# 82_SATA-SATA_PM0.net
KiCad netlist of a schematic drawn in Altium Designer
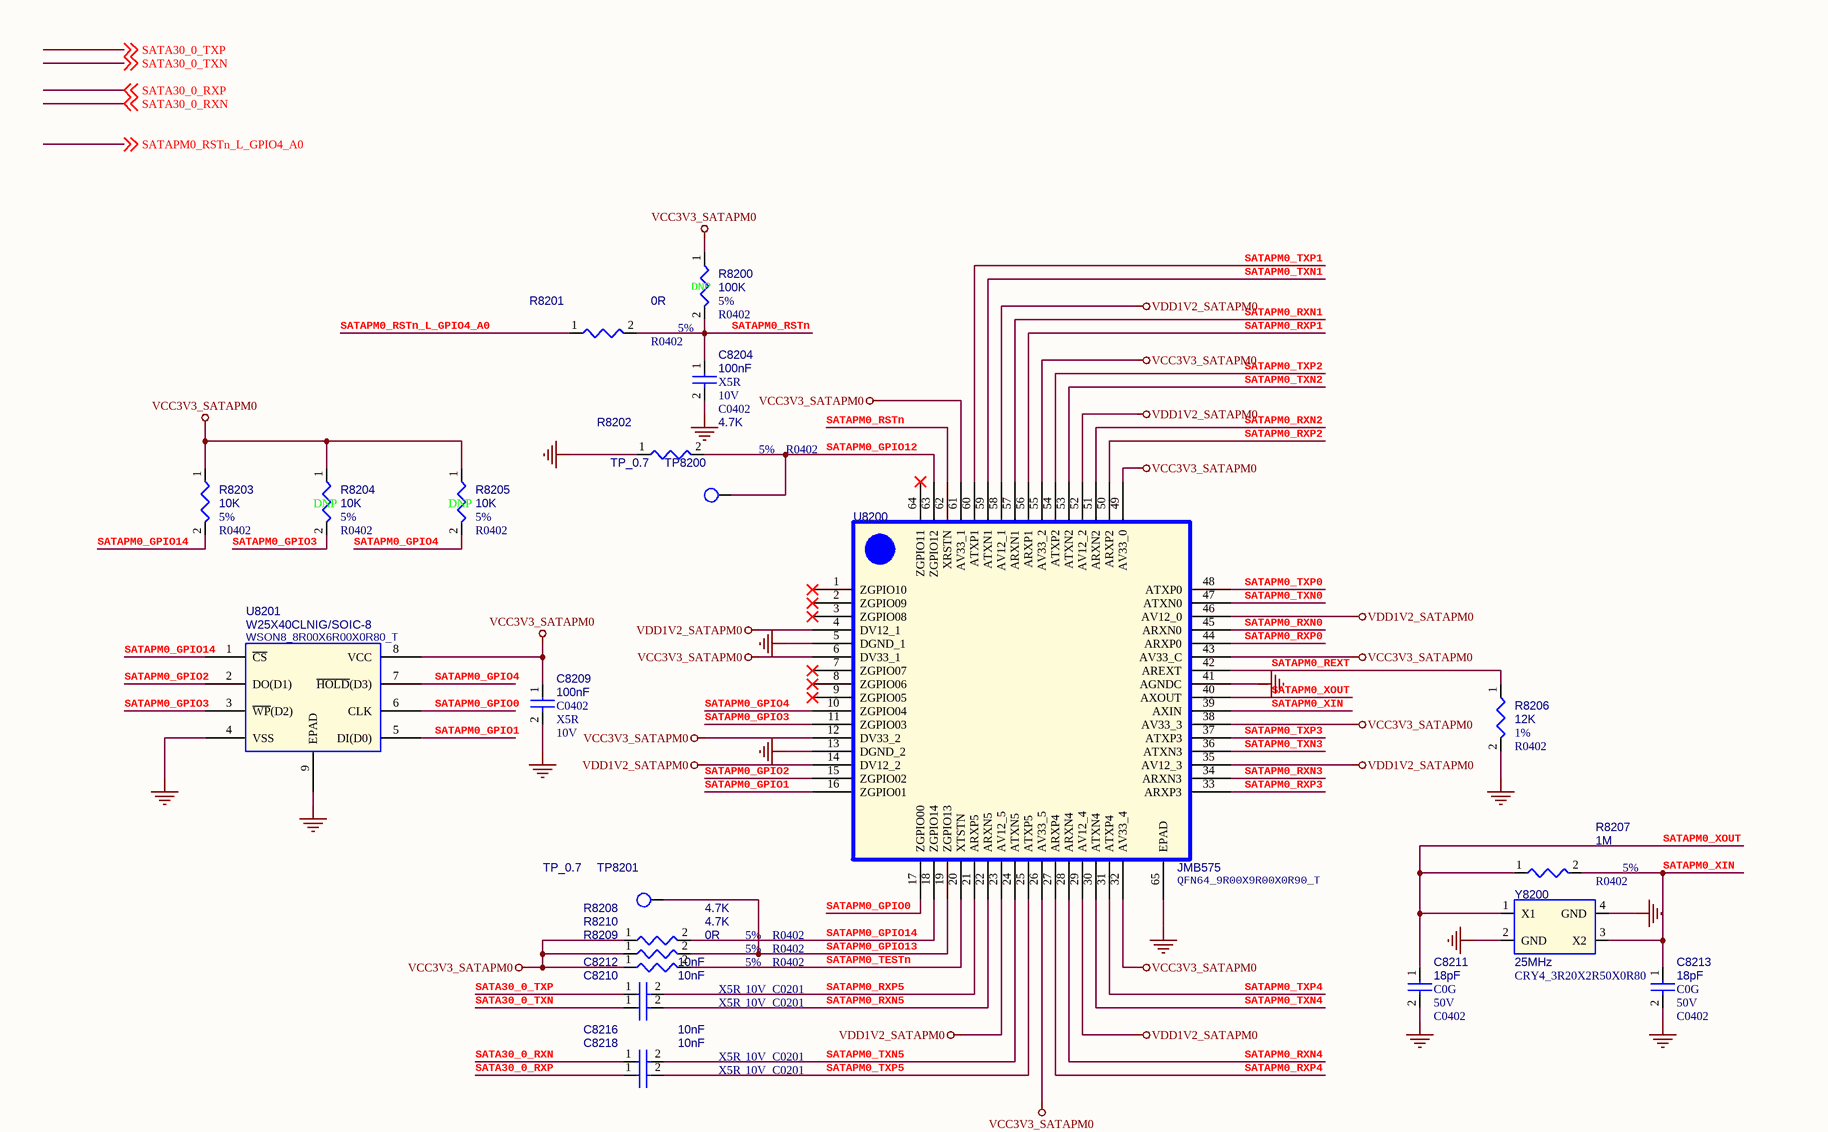
[diagram p0: 82.SATA-SATA PM0.SchDoc, top left]
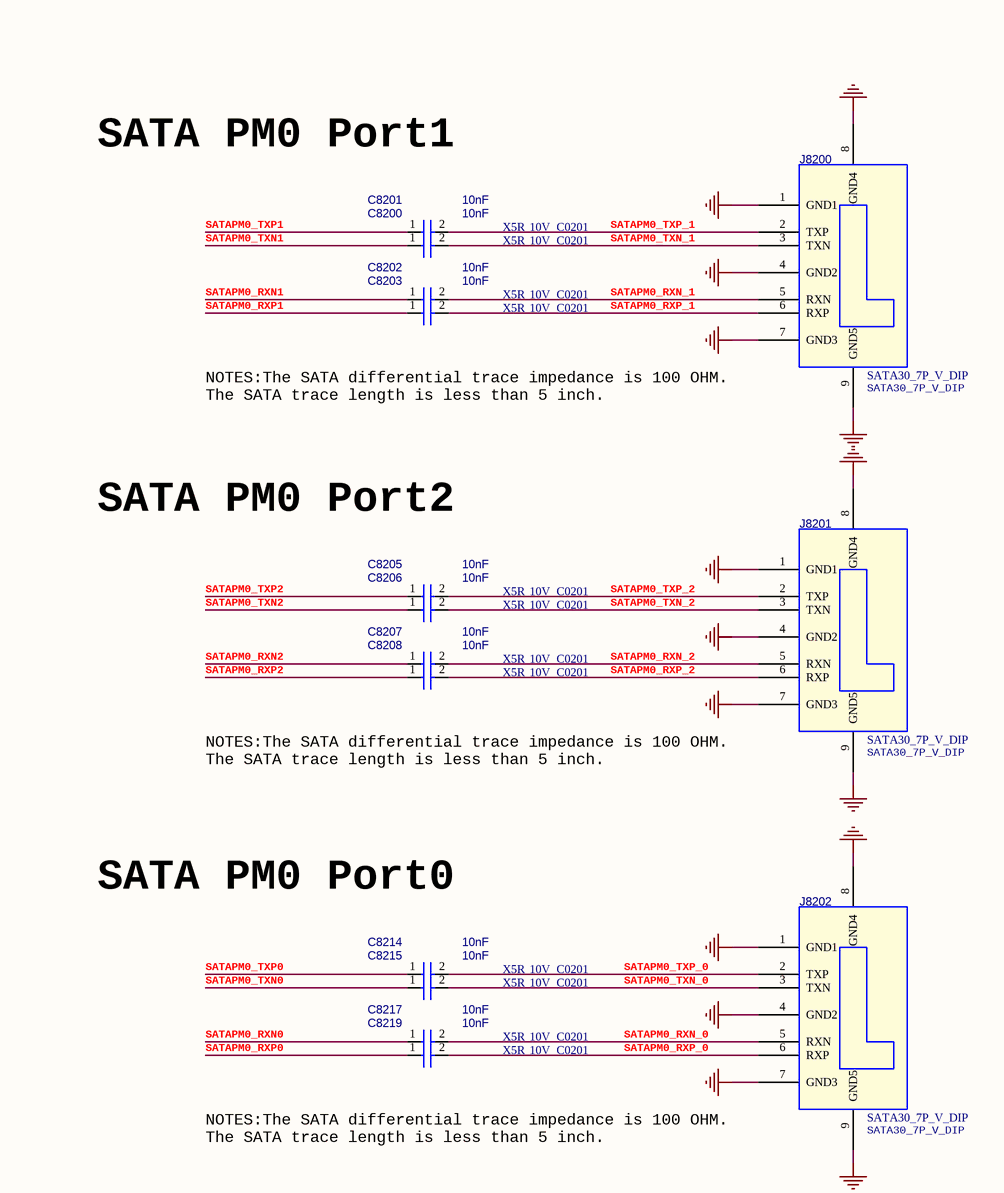
[diagram p1: 82.SATA-SATA PM0.SchDoc, top right]
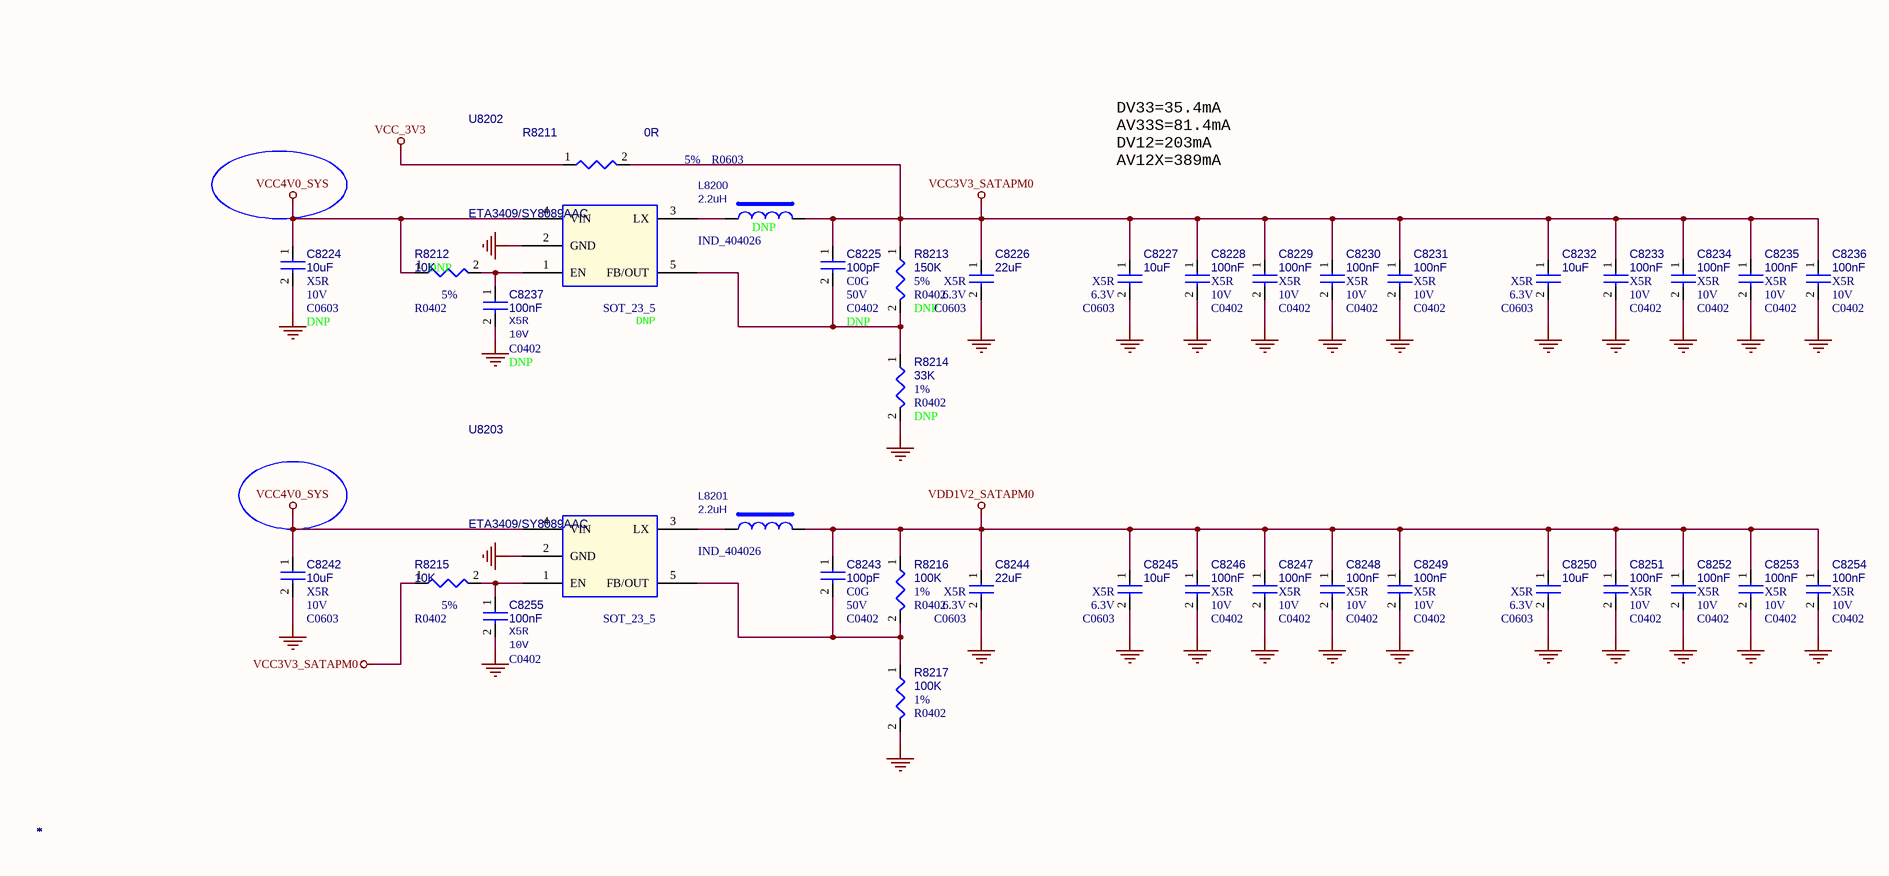
[diagram p2: 82.SATA-SATA PM0.SchDoc, bottom left]
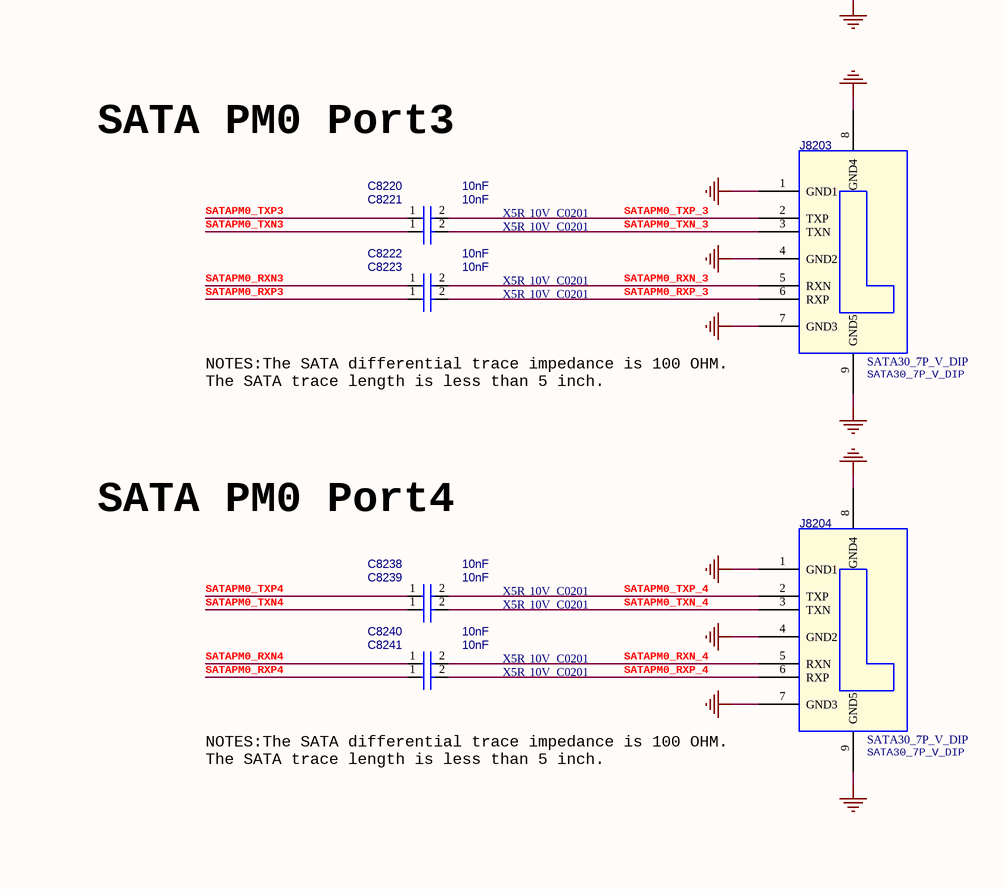
[diagram p3: 82.SATA-SATA PM0.SchDoc, bottom right]

(export (version "E")
  (design (tool "Eeschema 10.0.6"))
  (components
    (comp (ref "C8200")
      (value "*")
      (footprint "C0201")
      (description "cap,10.00nF,+/-10%,10V,X5R,C0201")
      (fields
        (field (name "VOLTAGE") "10V")
        (field (name "PCB FOOTPRINT") "C0201")
        (field (name "DIELECTRIC") "X5R")
        (field (name "MANUFACTURER") "TDK")
        (field (name "TOLERANCE") "10%")
        (field (name "ALTIUM_UNNAMED_1") "10nF")
        (field (name "CREATED BY") "JJJ")
      )
      (libsource (lib "*") (part "CAP NP"))
    )
    (comp (ref "C8201")
      (value "*")
      (footprint "C0201")
      (description "cap,10.00nF,+/-10%,10V,X5R,C0201")
      (fields
        (field (name "VOLTAGE") "10V")
        (field (name "PCB FOOTPRINT") "C0201")
        (field (name "DIELECTRIC") "X5R")
        (field (name "MANUFACTURER") "TDK")
        (field (name "TOLERANCE") "10%")
        (field (name "ALTIUM_UNNAMED_1") "10nF")
        (field (name "CREATED BY") "JJJ")
      )
      (libsource (lib "*") (part "CAP NP"))
    )
    (comp (ref "C8202")
      (value "*")
      (footprint "C0201")
      (description "cap,10.00nF,+/-10%,10V,X5R,C0201")
      (fields
        (field (name "VOLTAGE") "10V")
        (field (name "PCB FOOTPRINT") "C0201")
        (field (name "DIELECTRIC") "X5R")
        (field (name "MANUFACTURER") "TDK")
        (field (name "TOLERANCE") "10%")
        (field (name "ALTIUM_UNNAMED_1") "10nF")
        (field (name "CREATED BY") "JJJ")
      )
      (libsource (lib "*") (part "CAP NP"))
    )
    (comp (ref "C8203")
      (value "*")
      (footprint "C0201")
      (description "cap,10.00nF,+/-10%,10V,X5R,C0201")
      (fields
        (field (name "VOLTAGE") "10V")
        (field (name "PCB FOOTPRINT") "C0201")
        (field (name "DIELECTRIC") "X5R")
        (field (name "MANUFACTURER") "TDK")
        (field (name "TOLERANCE") "10%")
        (field (name "ALTIUM_UNNAMED_1") "10nF")
        (field (name "CREATED BY") "JJJ")
      )
      (libsource (lib "*") (part "CAP NP"))
    )
    (comp (ref "C8204")
      (value "*")
      (footprint "C0402")
      (description "cap,100.00nF,+/-10%,10V,X5R,C0402")
      (fields
        (field (name "VOLTAGE") "10V")
        (field (name "PCB FOOTPRINT") "C0402")
        (field (name "DIELECTRIC") "X5R")
        (field (name "TOLERANCE") "10%")
        (field (name "MANUFACTURER") "TDK")
        (field (name "ALTIUM_UNNAMED_1") "100nF")
        (field (name "CREATED BY") "JJJ")
      )
      (libsource (lib "*") (part "CAP NP"))
    )
    (comp (ref "C8205")
      (value "*")
      (footprint "C0201")
      (description "cap,10.00nF,+/-10%,10V,X5R,C0201")
      (fields
        (field (name "VOLTAGE") "10V")
        (field (name "PCB FOOTPRINT") "C0201")
        (field (name "DIELECTRIC") "X5R")
        (field (name "MANUFACTURER") "TDK")
        (field (name "TOLERANCE") "10%")
        (field (name "ALTIUM_UNNAMED_1") "10nF")
        (field (name "CREATED BY") "JJJ")
      )
      (libsource (lib "*") (part "CAP NP"))
    )
    (comp (ref "C8206")
      (value "*")
      (footprint "C0201")
      (description "cap,10.00nF,+/-10%,10V,X5R,C0201")
      (fields
        (field (name "VOLTAGE") "10V")
        (field (name "PCB FOOTPRINT") "C0201")
        (field (name "DIELECTRIC") "X5R")
        (field (name "MANUFACTURER") "TDK")
        (field (name "TOLERANCE") "10%")
        (field (name "ALTIUM_UNNAMED_1") "10nF")
        (field (name "CREATED BY") "JJJ")
      )
      (libsource (lib "*") (part "CAP NP"))
    )
    (comp (ref "C8207")
      (value "*")
      (footprint "C0201")
      (description "cap,10.00nF,+/-10%,10V,X5R,C0201")
      (fields
        (field (name "VOLTAGE") "10V")
        (field (name "PCB FOOTPRINT") "C0201")
        (field (name "DIELECTRIC") "X5R")
        (field (name "MANUFACTURER") "TDK")
        (field (name "TOLERANCE") "10%")
        (field (name "ALTIUM_UNNAMED_1") "10nF")
        (field (name "CREATED BY") "JJJ")
      )
      (libsource (lib "*") (part "CAP NP"))
    )
    (comp (ref "C8208")
      (value "*")
      (footprint "C0201")
      (description "cap,10.00nF,+/-10%,10V,X5R,C0201")
      (fields
        (field (name "VOLTAGE") "10V")
        (field (name "PCB FOOTPRINT") "C0201")
        (field (name "DIELECTRIC") "X5R")
        (field (name "MANUFACTURER") "TDK")
        (field (name "TOLERANCE") "10%")
        (field (name "ALTIUM_UNNAMED_1") "10nF")
        (field (name "CREATED BY") "JJJ")
      )
      (libsource (lib "*") (part "CAP NP"))
    )
    (comp (ref "C8209")
      (value "*")
      (footprint "C0402")
      (description "cap,100.00nF,+/-10%,10V,X5R,C0402")
      (fields
        (field (name "VOLTAGE") "10V")
        (field (name "PCB FOOTPRINT") "C0402")
        (field (name "DIELECTRIC") "X5R")
        (field (name "TOLERANCE") "10%")
        (field (name "MANUFACTURER") "TDK")
        (field (name "ALTIUM_UNNAMED_1") "100nF")
        (field (name "CREATED BY") "JJJ")
      )
      (libsource (lib "*") (part "CAP NP"))
    )
    (comp (ref "C8210")
      (value "*")
      (footprint "C0201")
      (description "cap,10.00nF,+/-10%,10V,X5R,C0201")
      (fields
        (field (name "VOLTAGE") "10V")
        (field (name "PCB FOOTPRINT") "C0201")
        (field (name "DIELECTRIC") "X5R")
        (field (name "TOLERANCE") "10%")
        (field (name "MANUFACTURER") "TDK")
        (field (name "ALTIUM_UNNAMED_1") "10nF")
        (field (name "CREATED BY") "JJJ")
      )
      (libsource (lib "*") (part "CAP NP"))
    )
    (comp (ref "C8211")
      (value "*")
      (footprint "C0402")
      (description "cap,18.00pF,+/-5%,50V,C0G,C0402")
      (fields
        (field (name "VOLTAGE") "50V")
        (field (name "PCB FOOTPRINT") "C0402")
        (field (name "DIELECTRIC") "C0G")
        (field (name "TOLERANCE") "5%")
        (field (name "MANUFACTURER") "TDK")
        (field (name "ALTIUM_UNNAMED_1") "18pF")
        (field (name "CREATED BY") "JJJ")
      )
      (libsource (lib "*") (part "CAP NP"))
    )
    (comp (ref "C8212")
      (value "*")
      (footprint "C0201")
      (description "cap,10.00nF,+/-10%,10V,X5R,C0201")
      (fields
        (field (name "VOLTAGE") "10V")
        (field (name "PCB FOOTPRINT") "C0201")
        (field (name "DIELECTRIC") "X5R")
        (field (name "TOLERANCE") "10%")
        (field (name "MANUFACTURER") "TDK")
        (field (name "ALTIUM_UNNAMED_1") "10nF")
        (field (name "CREATED BY") "JJJ")
      )
      (libsource (lib "*") (part "CAP NP"))
    )
    (comp (ref "C8213")
      (value "*")
      (footprint "C0402")
      (description "cap,18.00pF,+/-5%,50V,C0G,C0402")
      (fields
        (field (name "VOLTAGE") "50V")
        (field (name "PCB FOOTPRINT") "C0402")
        (field (name "DIELECTRIC") "C0G")
        (field (name "TOLERANCE") "5%")
        (field (name "MANUFACTURER") "TDK")
        (field (name "ALTIUM_UNNAMED_1") "18pF")
        (field (name "CREATED BY") "JJJ")
      )
      (libsource (lib "*") (part "CAP NP"))
    )
    (comp (ref "C8214")
      (value "*")
      (footprint "C0201")
      (description "cap,10.00nF,+/-10%,10V,X5R,C0201")
      (fields
        (field (name "VOLTAGE") "10V")
        (field (name "PCB FOOTPRINT") "C0201")
        (field (name "DIELECTRIC") "X5R")
        (field (name "MANUFACTURER") "TDK")
        (field (name "TOLERANCE") "10%")
        (field (name "ALTIUM_UNNAMED_1") "10nF")
        (field (name "CREATED BY") "JJJ")
      )
      (libsource (lib "*") (part "CAP NP"))
    )
    (comp (ref "C8215")
      (value "*")
      (footprint "C0201")
      (description "cap,10.00nF,+/-10%,10V,X5R,C0201")
      (fields
        (field (name "VOLTAGE") "10V")
        (field (name "PCB FOOTPRINT") "C0201")
        (field (name "DIELECTRIC") "X5R")
        (field (name "MANUFACTURER") "TDK")
        (field (name "TOLERANCE") "10%")
        (field (name "ALTIUM_UNNAMED_1") "10nF")
        (field (name "CREATED BY") "JJJ")
      )
      (libsource (lib "*") (part "CAP NP"))
    )
    (comp (ref "C8216")
      (value "*")
      (footprint "C0201")
      (description "cap,10.00nF,+/-10%,10V,X5R,C0201")
      (fields
        (field (name "VOLTAGE") "10V")
        (field (name "PCB FOOTPRINT") "C0201")
        (field (name "DIELECTRIC") "X5R")
        (field (name "TOLERANCE") "10%")
        (field (name "MANUFACTURER") "TDK")
        (field (name "ALTIUM_UNNAMED_1") "10nF")
        (field (name "CREATED BY") "JJJ")
      )
      (libsource (lib "*") (part "CAP NP"))
    )
    (comp (ref "C8217")
      (value "*")
      (footprint "C0201")
      (description "cap,10.00nF,+/-10%,10V,X5R,C0201")
      (fields
        (field (name "VOLTAGE") "10V")
        (field (name "PCB FOOTPRINT") "C0201")
        (field (name "DIELECTRIC") "X5R")
        (field (name "MANUFACTURER") "TDK")
        (field (name "TOLERANCE") "10%")
        (field (name "ALTIUM_UNNAMED_1") "10nF")
        (field (name "CREATED BY") "JJJ")
      )
      (libsource (lib "*") (part "CAP NP"))
    )
    (comp (ref "C8218")
      (value "*")
      (footprint "C0201")
      (description "cap,10.00nF,+/-10%,10V,X5R,C0201")
      (fields
        (field (name "VOLTAGE") "10V")
        (field (name "PCB FOOTPRINT") "C0201")
        (field (name "DIELECTRIC") "X5R")
        (field (name "TOLERANCE") "10%")
        (field (name "MANUFACTURER") "TDK")
        (field (name "ALTIUM_UNNAMED_1") "10nF")
        (field (name "CREATED BY") "JJJ")
      )
      (libsource (lib "*") (part "CAP NP"))
    )
    (comp (ref "C8219")
      (value "*")
      (footprint "C0201")
      (description "cap,10.00nF,+/-10%,10V,X5R,C0201")
      (fields
        (field (name "VOLTAGE") "10V")
        (field (name "PCB FOOTPRINT") "C0201")
        (field (name "DIELECTRIC") "X5R")
        (field (name "MANUFACTURER") "TDK")
        (field (name "TOLERANCE") "10%")
        (field (name "ALTIUM_UNNAMED_1") "10nF")
        (field (name "CREATED BY") "JJJ")
      )
      (libsource (lib "*") (part "CAP NP"))
    )
    (comp (ref "C8220")
      (value "*")
      (footprint "C0201")
      (description "cap,10.00nF,+/-10%,10V,X5R,C0201")
      (fields
        (field (name "VOLTAGE") "10V")
        (field (name "PCB FOOTPRINT") "C0201")
        (field (name "DIELECTRIC") "X5R")
        (field (name "MANUFACTURER") "TDK")
        (field (name "TOLERANCE") "10%")
        (field (name "ALTIUM_UNNAMED_1") "10nF")
        (field (name "CREATED BY") "JJJ")
      )
      (libsource (lib "*") (part "CAP NP"))
    )
    (comp (ref "C8221")
      (value "*")
      (footprint "C0201")
      (description "cap,10.00nF,+/-10%,10V,X5R,C0201")
      (fields
        (field (name "VOLTAGE") "10V")
        (field (name "PCB FOOTPRINT") "C0201")
        (field (name "DIELECTRIC") "X5R")
        (field (name "MANUFACTURER") "TDK")
        (field (name "TOLERANCE") "10%")
        (field (name "ALTIUM_UNNAMED_1") "10nF")
        (field (name "CREATED BY") "JJJ")
      )
      (libsource (lib "*") (part "CAP NP"))
    )
    (comp (ref "C8222")
      (value "*")
      (footprint "C0201")
      (description "cap,10.00nF,+/-10%,10V,X5R,C0201")
      (fields
        (field (name "VOLTAGE") "10V")
        (field (name "PCB FOOTPRINT") "C0201")
        (field (name "DIELECTRIC") "X5R")
        (field (name "MANUFACTURER") "TDK")
        (field (name "TOLERANCE") "10%")
        (field (name "ALTIUM_UNNAMED_1") "10nF")
        (field (name "CREATED BY") "JJJ")
      )
      (libsource (lib "*") (part "CAP NP"))
    )
    (comp (ref "C8223")
      (value "*")
      (footprint "C0201")
      (description "cap,10.00nF,+/-10%,10V,X5R,C0201")
      (fields
        (field (name "VOLTAGE") "10V")
        (field (name "PCB FOOTPRINT") "C0201")
        (field (name "DIELECTRIC") "X5R")
        (field (name "MANUFACTURER") "TDK")
        (field (name "TOLERANCE") "10%")
        (field (name "ALTIUM_UNNAMED_1") "10nF")
        (field (name "CREATED BY") "JJJ")
      )
      (libsource (lib "*") (part "CAP NP"))
    )
    (comp (ref "C8224")
      (value "*")
      (footprint "C0603")
      (description "cap,10.00uF,+/-10%,10V,X5R,C0603")
      (fields
        (field (name "VOLTAGE") "10V")
        (field (name "PCB FOOTPRINT") "C0603")
        (field (name "DIELECTRIC") "X5R")
        (field (name "MANUFACTURER") "TDK")
        (field (name "TOLERANCE") "10%")
        (field (name "OPTION") "DNP")
        (field (name "ALTIUM_UNNAMED_1") "10uF")
        (field (name "CREATED BY") "JJJ")
      )
      (libsource (lib "*") (part "CAP NP"))
    )
    (comp (ref "C8225")
      (value "*")
      (footprint "C0402")
      (description "cap,100.00pF,+/-10%,50V,C0G,C0402")
      (fields
        (field (name "VOLTAGE") "50V")
        (field (name "PCB FOOTPRINT") "C0402")
        (field (name "DIELECTRIC") "C0G")
        (field (name "TOLERANCE") "10%")
        (field (name "MANUFACTURER") "TDK")
        (field (name "OPTION") "DNP")
        (field (name "ALTIUM_UNNAMED_1") "100pF")
        (field (name "CREATED BY") "JJJ")
      )
      (libsource (lib "*") (part "CAP NP"))
    )
    (comp (ref "C8226")
      (value "*")
      (footprint "C0603")
      (description "cap,22.00uF,+/-20%,6.3V,X5R,C0603")
      (fields
        (field (name "VOLTAGE") "6.3V")
        (field (name "PCB FOOTPRINT") "C0603")
        (field (name "DIELECTRIC") "X5R")
        (field (name "MANUFACTURER") "TDK")
        (field (name "TOLERANCE") "20%")
        (field (name "ALTIUM_UNNAMED_1") "22uF")
        (field (name "CREATED BY") "JJJ")
      )
      (libsource (lib "*") (part "CAP NP"))
    )
    (comp (ref "C8227")
      (value "*")
      (footprint "C0603")
      (description "cap,10.00uF,+/-10%,6.3V,X5R,C0603")
      (fields
        (field (name "VOLTAGE") "6.3V")
        (field (name "PCB FOOTPRINT") "C0603")
        (field (name "DIELECTRIC") "X5R")
        (field (name "TOLERANCE") "10%")
        (field (name "MANUFACTURER") "TDK")
        (field (name "ALTIUM_UNNAMED_1") "10uF")
        (field (name "CREATED BY") "JJJ")
      )
      (libsource (lib "*") (part "CAP NP"))
    )
    (comp (ref "C8228")
      (value "*")
      (footprint "C0402")
      (description "cap,100.00nF,+/-10%,10V,X5R,C0402")
      (fields
        (field (name "VOLTAGE") "10V")
        (field (name "PCB FOOTPRINT") "C0402")
        (field (name "DIELECTRIC") "X5R")
        (field (name "MANUFACTURER") "TDK")
        (field (name "TOLERANCE") "10%")
        (field (name "ALTIUM_UNNAMED_1") "100nF")
        (field (name "CREATED BY") "JJJ")
      )
      (libsource (lib "*") (part "CAP NP"))
    )
    (comp (ref "C8229")
      (value "*")
      (footprint "C0402")
      (description "cap,100.00nF,+/-10%,10V,X5R,C0402")
      (fields
        (field (name "VOLTAGE") "10V")
        (field (name "PCB FOOTPRINT") "C0402")
        (field (name "DIELECTRIC") "X5R")
        (field (name "MANUFACTURER") "TDK")
        (field (name "TOLERANCE") "10%")
        (field (name "ALTIUM_UNNAMED_1") "100nF")
        (field (name "CREATED BY") "JJJ")
      )
      (libsource (lib "*") (part "CAP NP"))
    )
    (comp (ref "C8230")
      (value "*")
      (footprint "C0402")
      (description "cap,100.00nF,+/-10%,10V,X5R,C0402")
      (fields
        (field (name "VOLTAGE") "10V")
        (field (name "PCB FOOTPRINT") "C0402")
        (field (name "DIELECTRIC") "X5R")
        (field (name "MANUFACTURER") "TDK")
        (field (name "TOLERANCE") "10%")
        (field (name "ALTIUM_UNNAMED_1") "100nF")
        (field (name "CREATED BY") "JJJ")
      )
      (libsource (lib "*") (part "CAP NP"))
    )
    (comp (ref "C8231")
      (value "*")
      (footprint "C0402")
      (description "cap,100.00nF,+/-10%,10V,X5R,C0402")
      (fields
        (field (name "VOLTAGE") "10V")
        (field (name "PCB FOOTPRINT") "C0402")
        (field (name "DIELECTRIC") "X5R")
        (field (name "MANUFACTURER") "TDK")
        (field (name "TOLERANCE") "10%")
        (field (name "ALTIUM_UNNAMED_1") "100nF")
        (field (name "CREATED BY") "JJJ")
      )
      (libsource (lib "*") (part "CAP NP"))
    )
    (comp (ref "C8232")
      (value "*")
      (footprint "C0603")
      (description "cap,10.00uF,+/-10%,6.3V,X5R,C0603")
      (fields
        (field (name "VOLTAGE") "6.3V")
        (field (name "PCB FOOTPRINT") "C0603")
        (field (name "DIELECTRIC") "X5R")
        (field (name "TOLERANCE") "10%")
        (field (name "MANUFACTURER") "TDK")
        (field (name "ALTIUM_UNNAMED_1") "10uF")
        (field (name "CREATED BY") "JJJ")
      )
      (libsource (lib "*") (part "CAP NP"))
    )
    (comp (ref "C8233")
      (value "*")
      (footprint "C0402")
      (description "cap,100.00nF,+/-10%,10V,X5R,C0402")
      (fields
        (field (name "VOLTAGE") "10V")
        (field (name "PCB FOOTPRINT") "C0402")
        (field (name "DIELECTRIC") "X5R")
        (field (name "MANUFACTURER") "TDK")
        (field (name "TOLERANCE") "10%")
        (field (name "ALTIUM_UNNAMED_1") "100nF")
        (field (name "CREATED BY") "JJJ")
      )
      (libsource (lib "*") (part "CAP NP"))
    )
    (comp (ref "C8234")
      (value "*")
      (footprint "C0402")
      (description "cap,100.00nF,+/-10%,10V,X5R,C0402")
      (fields
        (field (name "VOLTAGE") "10V")
        (field (name "PCB FOOTPRINT") "C0402")
        (field (name "DIELECTRIC") "X5R")
        (field (name "MANUFACTURER") "TDK")
        (field (name "TOLERANCE") "10%")
        (field (name "ALTIUM_UNNAMED_1") "100nF")
        (field (name "CREATED BY") "JJJ")
      )
      (libsource (lib "*") (part "CAP NP"))
    )
    (comp (ref "C8235")
      (value "*")
      (footprint "C0402")
      (description "cap,100.00nF,+/-10%,10V,X5R,C0402")
      (fields
        (field (name "VOLTAGE") "10V")
        (field (name "PCB FOOTPRINT") "C0402")
        (field (name "DIELECTRIC") "X5R")
        (field (name "MANUFACTURER") "TDK")
        (field (name "TOLERANCE") "10%")
        (field (name "ALTIUM_UNNAMED_1") "100nF")
        (field (name "CREATED BY") "JJJ")
      )
      (libsource (lib "*") (part "CAP NP"))
    )
    (comp (ref "C8236")
      (value "*")
      (footprint "C0402")
      (description "cap,100.00nF,+/-10%,10V,X5R,C0402")
      (fields
        (field (name "VOLTAGE") "10V")
        (field (name "PCB FOOTPRINT") "C0402")
        (field (name "DIELECTRIC") "X5R")
        (field (name "MANUFACTURER") "TDK")
        (field (name "TOLERANCE") "10%")
        (field (name "ALTIUM_UNNAMED_1") "100nF")
        (field (name "CREATED BY") "JJJ")
      )
      (libsource (lib "*") (part "CAP NP"))
    )
    (comp (ref "C8237")
      (value "*")
      (footprint "C0402")
      (description "cap,100.00nF,+/-10%,10V,X5R,C0402")
      (fields
        (field (name "VOLTAGE") "10V")
        (field (name "PCB FOOTPRINT") "C0402")
        (field (name "DIELECTRIC") "X5R")
        (field (name "TOLERANCE") "10%")
        (field (name "MANUFACTURER") "TDK")
        (field (name "OPTION") "DNP")
        (field (name "ALTIUM_UNNAMED_1") "100nF")
        (field (name "CREATED BY") "JJJ")
      )
      (libsource (lib "*") (part "CAP NP"))
    )
    (comp (ref "C8238")
      (value "*")
      (footprint "C0201")
      (description "cap,10.00nF,+/-10%,10V,X5R,C0201")
      (fields
        (field (name "VOLTAGE") "10V")
        (field (name "PCB FOOTPRINT") "C0201")
        (field (name "DIELECTRIC") "X5R")
        (field (name "MANUFACTURER") "TDK")
        (field (name "TOLERANCE") "10%")
        (field (name "ALTIUM_UNNAMED_1") "10nF")
        (field (name "CREATED BY") "JJJ")
      )
      (libsource (lib "*") (part "CAP NP"))
    )
    (comp (ref "C8239")
      (value "*")
      (footprint "C0201")
      (description "cap,10.00nF,+/-10%,10V,X5R,C0201")
      (fields
        (field (name "VOLTAGE") "10V")
        (field (name "PCB FOOTPRINT") "C0201")
        (field (name "DIELECTRIC") "X5R")
        (field (name "MANUFACTURER") "TDK")
        (field (name "TOLERANCE") "10%")
        (field (name "ALTIUM_UNNAMED_1") "10nF")
        (field (name "CREATED BY") "JJJ")
      )
      (libsource (lib "*") (part "CAP NP"))
    )
    (comp (ref "C8240")
      (value "*")
      (footprint "C0201")
      (description "cap,10.00nF,+/-10%,10V,X5R,C0201")
      (fields
        (field (name "VOLTAGE") "10V")
        (field (name "PCB FOOTPRINT") "C0201")
        (field (name "DIELECTRIC") "X5R")
        (field (name "MANUFACTURER") "TDK")
        (field (name "TOLERANCE") "10%")
        (field (name "ALTIUM_UNNAMED_1") "10nF")
        (field (name "CREATED BY") "JJJ")
      )
      (libsource (lib "*") (part "CAP NP"))
    )
    (comp (ref "C8241")
      (value "*")
      (footprint "C0201")
      (description "cap,10.00nF,+/-10%,10V,X5R,C0201")
      (fields
        (field (name "VOLTAGE") "10V")
        (field (name "PCB FOOTPRINT") "C0201")
        (field (name "DIELECTRIC") "X5R")
        (field (name "MANUFACTURER") "TDK")
        (field (name "TOLERANCE") "10%")
        (field (name "ALTIUM_UNNAMED_1") "10nF")
        (field (name "CREATED BY") "JJJ")
      )
      (libsource (lib "*") (part "CAP NP"))
    )
    (comp (ref "C8242")
      (value "*")
      (footprint "C0603")
      (description "cap,10.00uF,+/-10%,10V,X5R,C0603")
      (fields
        (field (name "VOLTAGE") "10V")
        (field (name "PCB FOOTPRINT") "C0603")
        (field (name "DIELECTRIC") "X5R")
        (field (name "TOLERANCE") "10%")
        (field (name "MANUFACTURER") "TDK")
        (field (name "ALTIUM_UNNAMED_1") "10uF")
        (field (name "CREATED BY") "JJJ")
      )
      (libsource (lib "*") (part "CAP NP"))
    )
    (comp (ref "C8243")
      (value "*")
      (footprint "C0402")
      (description "cap,100.00pF,+/-10%,50V,C0G,C0402")
      (fields
        (field (name "VOLTAGE") "50V")
        (field (name "PCB FOOTPRINT") "C0402")
        (field (name "DIELECTRIC") "C0G")
        (field (name "MANUFACTURER") "TDK")
        (field (name "TOLERANCE") "10%")
        (field (name "ALTIUM_UNNAMED_1") "100pF")
        (field (name "CREATED BY") "JJJ")
      )
      (libsource (lib "*") (part "CAP NP"))
    )
    (comp (ref "C8244")
      (value "*")
      (footprint "C0603")
      (description "cap,22.00uF,+/-20%,6.3V,X5R,C0603")
      (fields
        (field (name "VOLTAGE") "6.3V")
        (field (name "PCB FOOTPRINT") "C0603")
        (field (name "DIELECTRIC") "X5R")
        (field (name "TOLERANCE") "20%")
        (field (name "MANUFACTURER") "TDK")
        (field (name "ALTIUM_UNNAMED_1") "22uF")
        (field (name "CREATED BY") "JJJ")
      )
      (libsource (lib "*") (part "CAP NP"))
    )
    (comp (ref "C8245")
      (value "*")
      (footprint "C0603")
      (description "cap,10.00uF,+/-10%,6.3V,X5R,C0603")
      (fields
        (field (name "VOLTAGE") "6.3V")
        (field (name "PCB FOOTPRINT") "C0603")
        (field (name "DIELECTRIC") "X5R")
        (field (name "TOLERANCE") "10%")
        (field (name "MANUFACTURER") "TDK")
        (field (name "ALTIUM_UNNAMED_1") "10uF")
        (field (name "CREATED BY") "JJJ")
      )
      (libsource (lib "*") (part "CAP NP"))
    )
    (comp (ref "C8246")
      (value "*")
      (footprint "C0402")
      (description "cap,100.00nF,+/-10%,10V,X5R,C0402")
      (fields
        (field (name "VOLTAGE") "10V")
        (field (name "PCB FOOTPRINT") "C0402")
        (field (name "DIELECTRIC") "X5R")
        (field (name "MANUFACTURER") "TDK")
        (field (name "TOLERANCE") "10%")
        (field (name "ALTIUM_UNNAMED_1") "100nF")
        (field (name "CREATED BY") "JJJ")
      )
      (libsource (lib "*") (part "CAP NP"))
    )
    (comp (ref "C8247")
      (value "*")
      (footprint "C0402")
      (description "cap,100.00nF,+/-10%,10V,X5R,C0402")
      (fields
        (field (name "VOLTAGE") "10V")
        (field (name "PCB FOOTPRINT") "C0402")
        (field (name "DIELECTRIC") "X5R")
        (field (name "MANUFACTURER") "TDK")
        (field (name "TOLERANCE") "10%")
        (field (name "ALTIUM_UNNAMED_1") "100nF")
        (field (name "CREATED BY") "JJJ")
      )
      (libsource (lib "*") (part "CAP NP"))
    )
    (comp (ref "C8248")
      (value "*")
      (footprint "C0402")
      (description "cap,100.00nF,+/-10%,10V,X5R,C0402")
      (fields
        (field (name "VOLTAGE") "10V")
        (field (name "PCB FOOTPRINT") "C0402")
        (field (name "DIELECTRIC") "X5R")
        (field (name "MANUFACTURER") "TDK")
        (field (name "TOLERANCE") "10%")
        (field (name "ALTIUM_UNNAMED_1") "100nF")
        (field (name "CREATED BY") "JJJ")
      )
      (libsource (lib "*") (part "CAP NP"))
    )
    (comp (ref "C8249")
      (value "*")
      (footprint "C0402")
      (description "cap,100.00nF,+/-10%,10V,X5R,C0402")
      (fields
        (field (name "VOLTAGE") "10V")
        (field (name "PCB FOOTPRINT") "C0402")
        (field (name "DIELECTRIC") "X5R")
        (field (name "MANUFACTURER") "TDK")
        (field (name "TOLERANCE") "10%")
        (field (name "ALTIUM_UNNAMED_1") "100nF")
        (field (name "CREATED BY") "JJJ")
      )
      (libsource (lib "*") (part "CAP NP"))
    )
    (comp (ref "C8250")
      (value "*")
      (footprint "C0603")
      (description "cap,10.00uF,+/-10%,6.3V,X5R,C0603")
      (fields
        (field (name "VOLTAGE") "6.3V")
        (field (name "PCB FOOTPRINT") "C0603")
        (field (name "DIELECTRIC") "X5R")
        (field (name "TOLERANCE") "10%")
        (field (name "MANUFACTURER") "TDK")
        (field (name "ALTIUM_UNNAMED_1") "10uF")
        (field (name "CREATED BY") "JJJ")
      )
      (libsource (lib "*") (part "CAP NP"))
    )
    (comp (ref "C8251")
      (value "*")
      (footprint "C0402")
      (description "cap,100.00nF,+/-10%,10V,X5R,C0402")
      (fields
        (field (name "VOLTAGE") "10V")
        (field (name "PCB FOOTPRINT") "C0402")
        (field (name "DIELECTRIC") "X5R")
        (field (name "MANUFACTURER") "TDK")
        (field (name "TOLERANCE") "10%")
        (field (name "ALTIUM_UNNAMED_1") "100nF")
        (field (name "CREATED BY") "JJJ")
      )
      (libsource (lib "*") (part "CAP NP"))
    )
    (comp (ref "C8252")
      (value "*")
      (footprint "C0402")
      (description "cap,100.00nF,+/-10%,10V,X5R,C0402")
      (fields
        (field (name "VOLTAGE") "10V")
        (field (name "PCB FOOTPRINT") "C0402")
        (field (name "DIELECTRIC") "X5R")
        (field (name "MANUFACTURER") "TDK")
        (field (name "TOLERANCE") "10%")
        (field (name "ALTIUM_UNNAMED_1") "100nF")
        (field (name "CREATED BY") "JJJ")
      )
      (libsource (lib "*") (part "CAP NP"))
    )
    (comp (ref "C8253")
      (value "*")
      (footprint "C0402")
      (description "cap,100.00nF,+/-10%,10V,X5R,C0402")
      (fields
        (field (name "VOLTAGE") "10V")
        (field (name "PCB FOOTPRINT") "C0402")
        (field (name "DIELECTRIC") "X5R")
        (field (name "MANUFACTURER") "TDK")
        (field (name "TOLERANCE") "10%")
        (field (name "ALTIUM_UNNAMED_1") "100nF")
        (field (name "CREATED BY") "JJJ")
      )
      (libsource (lib "*") (part "CAP NP"))
    )
    (comp (ref "C8254")
      (value "*")
      (footprint "C0402")
      (description "cap,100.00nF,+/-10%,10V,X5R,C0402")
      (fields
        (field (name "VOLTAGE") "10V")
        (field (name "PCB FOOTPRINT") "C0402")
        (field (name "DIELECTRIC") "X5R")
        (field (name "MANUFACTURER") "TDK")
        (field (name "TOLERANCE") "10%")
        (field (name "ALTIUM_UNNAMED_1") "100nF")
        (field (name "CREATED BY") "JJJ")
      )
      (libsource (lib "*") (part "CAP NP"))
    )
    (comp (ref "C8255")
      (value "*")
      (footprint "C0402")
      (description "cap,100.00nF,+/-10%,10V,X5R,C0402")
      (fields
        (field (name "VOLTAGE") "10V")
        (field (name "PCB FOOTPRINT") "C0402")
        (field (name "DIELECTRIC") "X5R")
        (field (name "MANUFACTURER") "TDK")
        (field (name "TOLERANCE") "10%")
        (field (name "ALTIUM_UNNAMED_1") "100nF")
        (field (name "CREATED BY") "JJJ")
      )
      (libsource (lib "*") (part "CAP NP"))
    )
    (comp (ref "J8200")
      (value "*")
      (footprint "SATA30_7P_V_DIP")
      (fields
        (field (name "PCB FOOTPRINT") "SATA30_7P_V_DIP")
        (field (name "ALTIUM_UNNAMED_1") "SATA30_7P_V_DIP")
      )
      (libsource (lib "*") (part "SATA_DIP_0"))
    )
    (comp (ref "J8201")
      (value "*")
      (footprint "SATA30_7P_V_DIP")
      (fields
        (field (name "PCB FOOTPRINT") "SATA30_7P_V_DIP")
        (field (name "ALTIUM_UNNAMED_1") "SATA30_7P_V_DIP")
      )
      (libsource (lib "*") (part "SATA_DIP_0"))
    )
    (comp (ref "J8202")
      (value "*")
      (footprint "SATA30_7P_V_DIP")
      (fields
        (field (name "PCB FOOTPRINT") "SATA30_7P_V_DIP")
        (field (name "ALTIUM_UNNAMED_1") "SATA30_7P_V_DIP")
      )
      (libsource (lib "*") (part "SATA_DIP_0"))
    )
    (comp (ref "J8203")
      (value "*")
      (footprint "SATA30_7P_V_DIP")
      (fields
        (field (name "PCB FOOTPRINT") "SATA30_7P_V_DIP")
        (field (name "ALTIUM_UNNAMED_1") "SATA30_7P_V_DIP")
      )
      (libsource (lib "*") (part "SATA_DIP_0"))
    )
    (comp (ref "J8204")
      (value "*")
      (footprint "SATA30_7P_V_DIP")
      (fields
        (field (name "PCB FOOTPRINT") "SATA30_7P_V_DIP")
        (field (name "ALTIUM_UNNAMED_1") "SATA30_7P_V_DIP")
      )
      (libsource (lib "*") (part "SATA_DIP_0"))
    )
    (comp (ref "L8200")
      (value "*")
      (footprint "IND_404026")
      (description "Power Inductor,2.2uH,0.2,IND_404026")
      (fields
        (field (name "PCB FOOTPRINT") "IND_404026")
        (field (name "TOLERANCE") "20%")
        (field (name "MANUFACTURER") "sunlord")
        (field (name "OPTION") "DNP")
        (field (name "ALTIUM_UNNAMED_1") "2.2uH")
        (field (name "CREATED BY") "YTL")
      )
      (libsource (lib "*") (part "INDUCTORS OF FERRITE_Dup1"))
    )
    (comp (ref "L8201")
      (value "*")
      (footprint "IND_404026")
      (description "Power Inductor,2.2uH,0.2,IND_404026")
      (fields
        (field (name "PCB FOOTPRINT") "IND_404026")
        (field (name "MANUFACTURER") "sunlord")
        (field (name "TOLERANCE") "20%")
        (field (name "ALTIUM_UNNAMED_1") "2.2uH")
        (field (name "CREATED BY") "YTL")
      )
      (libsource (lib "*") (part "INDUCTORS OF FERRITE_Dup1"))
    )
    (comp (ref "R8200")
      (value "*")
      (footprint "R0402")
      (description "НЁУГєсД¤µзЧи,100K,+/-5%,R0402,1/16W.")
      (fields
        (field (name "PCB FOOTPRINT") "R0402")
        (field (name "TOLERANCE") "5%")
        (field (name "MANUFACTURER") "YAGEO")
        (field (name "OPTION") "DNP")
        (field (name "ALTIUM_UNNAMED_1") "100K")
        (field (name "CREATED BY") "YTL")
      )
      (libsource (lib "*") (part "RESISTOR_Dup1"))
    )
    (comp (ref "R8201")
      (value "*")
      (footprint "R0402")
      (description "НЁУГєсД¤µзЧи,0R,+/-5%,R0402,1/16W.")
      (fields
        (field (name "PCB FOOTPRINT") "R0402")
        (field (name "TOLERANCE") "5%")
        (field (name "MANUFACTURER") "YAGEO")
        (field (name "ALTIUM_UNNAMED_1") "0R")
        (field (name "CREATED BY") "YTL")
      )
      (libsource (lib "*") (part "RESISTOR_Dup1"))
    )
    (comp (ref "R8202")
      (value "*")
      (footprint "R0402")
      (description "НЁУГєсД¤µзЧи,4K7,+/-5%,R0402,1/16W.")
      (fields
        (field (name "PCB FOOTPRINT") "R0402")
        (field (name "TOLERANCE") "5%")
        (field (name "MANUFACTURER") "YAGEO")
        (field (name "ALTIUM_UNNAMED_1") "4.7K")
        (field (name "CREATED BY") "YTL")
      )
      (libsource (lib "*") (part "RESISTOR_Dup1"))
    )
    (comp (ref "R8203")
      (value "*")
      (footprint "R0402")
      (description "НЁУГєсД¤µзЧи,10K,+/-5%,R0402,1/16W.")
      (fields
        (field (name "PCB FOOTPRINT") "R0402")
        (field (name "TOLERANCE") "5%")
        (field (name "MANUFACTURER") "YAGEO")
        (field (name "ALTIUM_UNNAMED_1") "10K")
        (field (name "CREATED BY") "YTL")
      )
      (libsource (lib "*") (part "RESISTOR_Dup1"))
    )
    (comp (ref "R8204")
      (value "*")
      (footprint "R0402")
      (description "НЁУГєсД¤µзЧи,10K,+/-5%,R0402,1/16W.")
      (fields
        (field (name "PCB FOOTPRINT") "R0402")
        (field (name "TOLERANCE") "5%")
        (field (name "OPTION") "DNP")
        (field (name "MANUFACTURER") "YAGEO")
        (field (name "ALTIUM_UNNAMED_1") "10K")
        (field (name "CREATED BY") "YTL")
      )
      (libsource (lib "*") (part "RESISTOR_Dup1"))
    )
    (comp (ref "R8205")
      (value "*")
      (footprint "R0402")
      (description "НЁУГєсД¤µзЧи,10K,+/-5%,R0402,1/16W.")
      (fields
        (field (name "PCB FOOTPRINT") "R0402")
        (field (name "TOLERANCE") "5%")
        (field (name "MANUFACTURER") "YAGEO")
        (field (name "OPTION") "DNP")
        (field (name "ALTIUM_UNNAMED_1") "10K")
        (field (name "CREATED BY") "YTL")
      )
      (libsource (lib "*") (part "RESISTOR_Dup1"))
    )
    (comp (ref "R8206")
      (value "*")
      (footprint "R0402")
      (description "НЁУГєсД¤µзЧи,12K,+/-1%,R0402,1/16W.")
      (fields
        (field (name "PCB FOOTPRINT") "R0402")
        (field (name "TOLERANCE") "1%")
        (field (name "MANUFACTURER") "YAGEO")
        (field (name "ALTIUM_UNNAMED_1") "12K")
        (field (name "CREATED BY") "YTL")
      )
      (libsource (lib "*") (part "RESISTOR_Dup1"))
    )
    (comp (ref "R8207")
      (value "*")
      (footprint "R0402")
      (description "НЁУГєсД¤µзЧи,1M,+/-5%,R0402,1/16W.")
      (fields
        (field (name "PCB FOOTPRINT") "R0402")
        (field (name "TOLERANCE") "5%")
        (field (name "MANUFACTURER") "YAGEO")
        (field (name "ALTIUM_UNNAMED_1") "1M")
        (field (name "CREATED BY") "YTL")
      )
      (libsource (lib "*") (part "RESISTOR_Dup1"))
    )
    (comp (ref "R8208")
      (value "*")
      (footprint "R0402")
      (description "НЁУГєсД¤µзЧи,4K7,+/-5%,R0402,1/16W.")
      (fields
        (field (name "PCB FOOTPRINT") "R0402")
        (field (name "TOLERANCE") "5%")
        (field (name "MANUFACTURER") "YAGEO")
        (field (name "ALTIUM_UNNAMED_1") "4.7K")
        (field (name "CREATED BY") "YTL")
      )
      (libsource (lib "*") (part "RESISTOR_Dup1"))
    )
    (comp (ref "R8209")
      (value "*")
      (footprint "R0402")
      (description "НЁУГєсД¤µзЧи,0R,+/-5%,R0402,1/16W.")
      (fields
        (field (name "PCB FOOTPRINT") "R0402")
        (field (name "TOLERANCE") "5%")
        (field (name "MANUFACTURER") "YAGEO")
        (field (name "ALTIUM_UNNAMED_1") "0R")
        (field (name "CREATED BY") "YTL")
      )
      (libsource (lib "*") (part "RESISTOR_Dup1"))
    )
    (comp (ref "R8210")
      (value "*")
      (footprint "R0402")
      (description "НЁУГєсД¤µзЧи,4K7,+/-5%,R0402,1/16W.")
      (fields
        (field (name "PCB FOOTPRINT") "R0402")
        (field (name "TOLERANCE") "5%")
        (field (name "MANUFACTURER") "YAGEO")
        (field (name "ALTIUM_UNNAMED_1") "4.7K")
        (field (name "CREATED BY") "YTL")
      )
      (libsource (lib "*") (part "RESISTOR_Dup1"))
    )
    (comp (ref "R8211")
      (value "*")
      (footprint "R0402")
      (description "НЁУГєсД¤µзЧи,0R,+/-5%,R0603,1/10W.")
      (fields
        (field (name "PCB FOOTPRINT") "R0603")
        (field (name "TOLERANCE") "5%")
        (field (name "MANUFACTURER") "YAGEO")
        (field (name "ALTIUM_UNNAMED_1") "0R")
        (field (name "CREATED BY") "YTL")
      )
      (libsource (lib "*") (part "RESISTOR_Dup1"))
    )
    (comp (ref "R8212")
      (value "*")
      (footprint "R0402")
      (description "НЁУГєсД¤µзЧи,10K,+/-5%,R0402,1/16W.")
      (fields
        (field (name "PCB FOOTPRINT") "R0402")
        (field (name "TOLERANCE") "5%")
        (field (name "MANUFACTURER") "YAGEO")
        (field (name "OPTION") "DNP")
        (field (name "ALTIUM_UNNAMED_1") "10K")
        (field (name "CREATED BY") "YTL")
      )
      (libsource (lib "*") (part "RESISTOR_Dup1"))
    )
    (comp (ref "R8213")
      (value "*")
      (footprint "R0402")
      (description "НЁУГєсД¤µзЧи,150K,+/-5%,R0402,1/16W.")
      (fields
        (field (name "PCB FOOTPRINT") "R0402")
        (field (name "TOLERANCE") "5%")
        (field (name "OPTION") "DNP")
        (field (name "MANUFACTURER") "YAGEO")
        (field (name "ALTIUM_UNNAMED_1") "150K")
        (field (name "CREATED BY") "YTL")
      )
      (libsource (lib "*") (part "RESISTOR_Dup1"))
    )
    (comp (ref "R8214")
      (value "*")
      (footprint "R0402")
      (description "НЁУГєсД¤µзЧи,33K,+/-1%,R0402,1/16W.")
      (fields
        (field (name "PCB FOOTPRINT") "R0402")
        (field (name "TOLERANCE") "1%")
        (field (name "MANUFACTURER") "YAGEO")
        (field (name "OPTION") "DNP")
        (field (name "ALTIUM_UNNAMED_1") "33K")
        (field (name "CREATED BY") "YTL")
      )
      (libsource (lib "*") (part "RESISTOR_Dup1"))
    )
    (comp (ref "R8215")
      (value "*")
      (footprint "R0402")
      (description "НЁУГєсД¤µзЧи,10K,+/-5%,R0402,1/16W.")
      (fields
        (field (name "PCB FOOTPRINT") "R0402")
        (field (name "TOLERANCE") "5%")
        (field (name "MANUFACTURER") "YAGEO")
        (field (name "ALTIUM_UNNAMED_1") "10K")
        (field (name "CREATED BY") "YTL")
      )
      (libsource (lib "*") (part "RESISTOR_Dup1"))
    )
    (comp (ref "R8216")
      (value "*")
      (footprint "R0402")
      (description "НЁУГєсД¤µзЧи,100K,+/-1%,R0402,1/16W.")
      (fields
        (field (name "PCB FOOTPRINT") "R0402")
        (field (name "TOLERANCE") "1%")
        (field (name "MANUFACTURER") "YAGEO")
        (field (name "ALTIUM_UNNAMED_1") "100K")
        (field (name "CREATED BY") "YTL")
      )
      (libsource (lib "*") (part "RESISTOR_Dup1"))
    )
    (comp (ref "R8217")
      (value "*")
      (footprint "R0402")
      (description "НЁУГєсД¤µзЧи,100K,+/-1%,R0402,1/16W.")
      (fields
        (field (name "PCB FOOTPRINT") "R0402")
        (field (name "TOLERANCE") "1%")
        (field (name "MANUFACTURER") "YAGEO")
        (field (name "ALTIUM_UNNAMED_1") "100K")
        (field (name "CREATED BY") "YTL")
      )
      (libsource (lib "*") (part "RESISTOR_Dup1"))
    )
    (comp (ref "TP8200")
      (value "*")
      (footprint "TEST")
      (description "Test Point 0.7mm")
      (fields (field (name "ALTIUM_UNNAMED_1") "TP_0.7") (field (name "CREATED BY") "JJJ"))
      (libsource (lib "*") (part "TP"))
    )
    (comp (ref "TP8201")
      (value "*")
      (footprint "TEST")
      (description "Test Point 0.7mm")
      (fields (field (name "ALTIUM_UNNAMED_1") "TP_0.7") (field (name "CREATED BY") "JJJ"))
      (libsource (lib "*") (part "TP"))
    )
    (comp (ref "U8200")
      (value "*")
      (footprint "QFN64")
      (fields
        (field (name "PCB FOOTPRINT") "QFN64_9R00X9R00X0R90_T")
        (field (name "ALTIUM_UNNAMED_1") "JMB575")
      )
      (libsource (lib "*") (part "JMB575"))
    )
    (comp (ref "U8201")
      (value "*")
      (footprint "WSON8_8R00X6R00X0R80_T")
      (description "256M-bit Serial Flash;32M-byte;3.3V Uniform Sector;Dual and Quad Serial Flash;")
      (fields
        (field (name "PCB FOOTPRINT") "WSON8_8R00X6R00X0R80_T")
        (field (name "MANUFACTURER") "GigaDevice")
        (field (name "ALTIUM_UNNAMED_1") "W25X40CLNIG/SOIC-8")
        (field (name "CREATED BY") "JJJ")
      )
      (libsource (lib "*") (part "SPI_FLASH_8PIN_T_0"))
    )
    (comp (ref "U8202")
      (value "*")
      (footprint "SOT_23_5")
      (description "High Efficiency 5.5V, 2A continuous, 3A peak, 1MHz Synchronous Step Down Regulator")
      (fields
        (field (name "PCB FOOTPRINT") "SOT_23_5")
        (field (name "MANUFACTURER") "SilergyЈЁОщБ¦ЅЬЈ©")
        (field (name "OPTION") "DNP")
        (field (name "ALTIUM_UNNAMED_1") "ETA3409/SY8089AAC")
        (field (name "CREATED BY") "JJJ")
      )
      (libsource (lib "*") (part "DCDC_SY8088"))
    )
    (comp (ref "U8203")
      (value "*")
      (footprint "SOT_23_5")
      (description "High Efficiency 5.5V, 2A continuous, 3A peak, 1MHz Synchronous Step Down Regulator")
      (fields
        (field (name "PCB FOOTPRINT") "SOT_23_5")
        (field (name "MANUFACTURER") "SilergyЈЁОщБ¦ЅЬЈ©")
        (field (name "ALTIUM_UNNAMED_1") "ETA3409/SY8089AAC")
        (field (name "CREATED BY") "JJJ")
      )
      (libsource (lib "*") (part "DCDC_SY8088"))
    )
    (comp (ref "Y8200")
      (value "*")
      (footprint "CRY-3225")
      (description "ОЮФґѕ§ХсЈ¬25MЈ¬3225,ЎА10ppmЈ¬10pFЈ¬Hosonic")
      (fields
        (field (name "PCB FOOTPRINT") "CRY4_3R20X2R50X0R80")
        (field (name "MANUFACTURER") "Hosonic(єиРЗµзЧУ)")
        (field (name "ALTIUM_UNNAMED_1") "25MHz")
        (field (name "CREATED BY") "JJJ")
      )
      (libsource (lib "*") (part "CRYSTAL_4P"))
    )
  )
  (nets
    (net (code "1") (name "/SATAPM0_GPIO0") (class "Default")
      (node (ref "U8200") (pin "17") (pinfunction "ZGPIO00_17") (pintype "passive"))
      (node (ref "U8201") (pin "6") (pinfunction "CLK_6") (pintype "passive"))
    )
    (net (code "2") (name "/SATAPM0_GPIO1") (class "Default")
      (node (ref "U8200") (pin "16") (pinfunction "ZGPIO01_16") (pintype "passive"))
      (node (ref "U8201") (pin "5") (pinfunction "DI(D0)_5") (pintype "passive"))
    )
    (net (code "3") (name "/SATAPM0_GPIO2") (class "Default")
      (node (ref "U8200") (pin "15") (pinfunction "ZGPIO02_15") (pintype "passive"))
      (node (ref "U8201") (pin "2") (pinfunction "DO(D1)_2") (pintype "passive"))
    )
    (net (code "4") (name "/SATAPM0_GPIO3") (class "Default")
      (node (ref "R8204") (pin "2") (pinfunction "2_2") (pintype "passive"))
      (node (ref "U8200") (pin "11") (pinfunction "ZGPIO03_11") (pintype "passive"))
      (node (ref "U8201") (pin "3") (pinfunction "~{WP}(D2)_3") (pintype "passive"))
    )
    (net (code "5") (name "/SATAPM0_GPIO4") (class "Default")
      (node (ref "R8205") (pin "2") (pinfunction "2_2") (pintype "passive"))
      (node (ref "U8200") (pin "10") (pinfunction "ZGPIO04_10") (pintype "passive"))
      (node (ref "U8201") (pin "7") (pinfunction "~{HOLD}(D3)_7") (pintype "passive"))
    )
    (net (code "6") (name "/SATAPM0_GPIO12") (class "Default")
      (node (ref "R8202") (pin "2") (pinfunction "2_2") (pintype "passive"))
      (node (ref "TP8200") (pin "1") (pinfunction "1_1") (pintype "passive"))
      (node (ref "U8200") (pin "63") (pinfunction "ZGPIO12_63") (pintype "passive"))
    )
    (net (code "7") (name "/SATAPM0_GPIO13") (class "Default")
      (node (ref "R8210") (pin "2") (pinfunction "2_2") (pintype "passive"))
      (node (ref "TP8201") (pin "1") (pinfunction "1_1") (pintype "passive"))
      (node (ref "U8200") (pin "19") (pinfunction "ZGPIO13_19") (pintype "passive"))
    )
    (net (code "8") (name "/SATAPM0_GPIO14") (class "Default")
      (node (ref "R8203") (pin "2") (pinfunction "2_2") (pintype "passive"))
      (node (ref "R8208") (pin "2") (pinfunction "2_2") (pintype "passive"))
      (node (ref "U8200") (pin "18") (pinfunction "ZGPIO14_18") (pintype "passive"))
      (node (ref "U8201") (pin "1") (pinfunction "~{CS}_1") (pintype "passive"))
    )
    (net (code "9") (name "/SATAPM0_REXT") (class "Default")
      (node (ref "R8206") (pin "1") (pinfunction "1_1") (pintype "passive"))
      (node (ref "U8200") (pin "42") (pinfunction "AREXT_42") (pintype "passive"))
    )
    (net (code "10") (name "/SATAPM0_RSTn") (class "Default")
      (node (ref "C8204") (pin "1") (pinfunction "1_1") (pintype "passive"))
      (node (ref "R8200") (pin "2") (pinfunction "2_2") (pintype "passive"))
      (node (ref "R8201") (pin "2") (pinfunction "2_2") (pintype "passive"))
      (node (ref "U8200") (pin "62") (pinfunction "XRSTN_62") (pintype "passive"))
    )
    (net (code "11") (name "/SATAPM0_RXN0") (class "Default")
      (node (ref "C8217") (pin "1") (pinfunction "1_1") (pintype "passive"))
      (node (ref "U8200") (pin "45") (pinfunction "ARXN0_45") (pintype "passive"))
    )
    (net (code "12") (name "/SATAPM0_RXN1") (class "Default")
      (node (ref "C8202") (pin "1") (pinfunction "1_1") (pintype "passive"))
      (node (ref "U8200") (pin "57") (pinfunction "ARXN1_57") (pintype "passive"))
    )
    (net (code "13") (name "/SATAPM0_RXN2") (class "Default")
      (node (ref "C8207") (pin "1") (pinfunction "1_1") (pintype "passive"))
      (node (ref "U8200") (pin "51") (pinfunction "ARXN2_51") (pintype "passive"))
    )
    (net (code "14") (name "/SATAPM0_RXN3") (class "Default")
      (node (ref "C8222") (pin "1") (pinfunction "1_1") (pintype "passive"))
      (node (ref "U8200") (pin "34") (pinfunction "ARXN3_34") (pintype "passive"))
    )
    (net (code "15") (name "/SATAPM0_RXN4") (class "Default")
      (node (ref "C8240") (pin "1") (pinfunction "1_1") (pintype "passive"))
      (node (ref "U8200") (pin "28") (pinfunction "ARXN4_28") (pintype "passive"))
    )
    (net (code "16") (name "/SATAPM0_RXN5") (class "Default")
      (node (ref "C8210") (pin "2") (pinfunction "2_2") (pintype "passive"))
      (node (ref "U8200") (pin "22") (pinfunction "ARXN5_22") (pintype "passive"))
    )
    (net (code "17") (name "/SATAPM0_RXN_0") (class "Default")
      (node (ref "C8217") (pin "2") (pinfunction "2_2") (pintype "passive"))
      (node (ref "J8202") (pin "5") (pinfunction "RXN_5") (pintype "passive"))
    )
    (net (code "18") (name "/SATAPM0_RXN_1") (class "Default")
      (node (ref "C8202") (pin "2") (pinfunction "2_2") (pintype "passive"))
      (node (ref "J8200") (pin "5") (pinfunction "RXN_5") (pintype "passive"))
    )
    (net (code "19") (name "/SATAPM0_RXN_2") (class "Default")
      (node (ref "C8207") (pin "2") (pinfunction "2_2") (pintype "passive"))
      (node (ref "J8201") (pin "5") (pinfunction "RXN_5") (pintype "passive"))
    )
    (net (code "20") (name "/SATAPM0_RXN_3") (class "Default")
      (node (ref "C8222") (pin "2") (pinfunction "2_2") (pintype "passive"))
      (node (ref "J8203") (pin "5") (pinfunction "RXN_5") (pintype "passive"))
    )
    (net (code "21") (name "/SATAPM0_RXN_4") (class "Default")
      (node (ref "C8240") (pin "2") (pinfunction "2_2") (pintype "passive"))
      (node (ref "J8204") (pin "5") (pinfunction "RXN_5") (pintype "passive"))
    )
    (net (code "22") (name "/SATAPM0_RXP0") (class "Default")
      (node (ref "C8219") (pin "1") (pinfunction "1_1") (pintype "passive"))
      (node (ref "U8200") (pin "44") (pinfunction "ARXP0_44") (pintype "passive"))
    )
    (net (code "23") (name "/SATAPM0_RXP1") (class "Default")
      (node (ref "C8203") (pin "1") (pinfunction "1_1") (pintype "passive"))
      (node (ref "U8200") (pin "56") (pinfunction "ARXP1_56") (pintype "passive"))
    )
    (net (code "24") (name "/SATAPM0_RXP2") (class "Default")
      (node (ref "C8208") (pin "1") (pinfunction "1_1") (pintype "passive"))
      (node (ref "U8200") (pin "50") (pinfunction "ARXP2_50") (pintype "passive"))
    )
    (net (code "25") (name "/SATAPM0_RXP3") (class "Default")
      (node (ref "C8223") (pin "1") (pinfunction "1_1") (pintype "passive"))
      (node (ref "U8200") (pin "33") (pinfunction "ARXP3_33") (pintype "passive"))
    )
    (net (code "26") (name "/SATAPM0_RXP4") (class "Default")
      (node (ref "C8241") (pin "1") (pinfunction "1_1") (pintype "passive"))
      (node (ref "U8200") (pin "27") (pinfunction "ARXP4_27") (pintype "passive"))
    )
    (net (code "27") (name "/SATAPM0_RXP5") (class "Default")
      (node (ref "C8212") (pin "2") (pinfunction "2_2") (pintype "passive"))
      (node (ref "U8200") (pin "21") (pinfunction "ARXP5_21") (pintype "passive"))
    )
    (net (code "28") (name "/SATAPM0_RXP_0") (class "Default")
      (node (ref "C8219") (pin "2") (pinfunction "2_2") (pintype "passive"))
      (node (ref "J8202") (pin "6") (pinfunction "RXP_6") (pintype "passive"))
    )
    (net (code "29") (name "/SATAPM0_RXP_1") (class "Default")
      (node (ref "C8203") (pin "2") (pinfunction "2_2") (pintype "passive"))
      (node (ref "J8200") (pin "6") (pinfunction "RXP_6") (pintype "passive"))
    )
    (net (code "30") (name "/SATAPM0_RXP_2") (class "Default")
      (node (ref "C8208") (pin "2") (pinfunction "2_2") (pintype "passive"))
      (node (ref "J8201") (pin "6") (pinfunction "RXP_6") (pintype "passive"))
    )
    (net (code "31") (name "/SATAPM0_RXP_3") (class "Default")
      (node (ref "C8223") (pin "2") (pinfunction "2_2") (pintype "passive"))
      (node (ref "J8203") (pin "6") (pinfunction "RXP_6") (pintype "passive"))
    )
    (net (code "32") (name "/SATAPM0_RXP_4") (class "Default")
      (node (ref "C8241") (pin "2") (pinfunction "2_2") (pintype "passive"))
      (node (ref "J8204") (pin "6") (pinfunction "RXP_6") (pintype "passive"))
    )
    (net (code "33") (name "/SATAPM0_TESTn") (class "Default")
      (node (ref "R8209") (pin "2") (pinfunction "2_2") (pintype "passive"))
      (node (ref "U8200") (pin "20") (pinfunction "XTSTN_20") (pintype "passive"))
    )
    (net (code "34") (name "/SATAPM0_TXN0") (class "Default")
      (node (ref "C8215") (pin "1") (pinfunction "1_1") (pintype "passive"))
      (node (ref "U8200") (pin "47") (pinfunction "ATXN0_47") (pintype "passive"))
    )
    (net (code "35") (name "/SATAPM0_TXN1") (class "Default")
      (node (ref "C8200") (pin "1") (pinfunction "1_1") (pintype "passive"))
      (node (ref "U8200") (pin "59") (pinfunction "ATXN1_59") (pintype "passive"))
    )
    (net (code "36") (name "/SATAPM0_TXN2") (class "Default")
      (node (ref "C8206") (pin "1") (pinfunction "1_1") (pintype "passive"))
      (node (ref "U8200") (pin "53") (pinfunction "ATXN2_53") (pintype "passive"))
    )
    (net (code "37") (name "/SATAPM0_TXN3") (class "Default")
      (node (ref "C8221") (pin "1") (pinfunction "1_1") (pintype "passive"))
      (node (ref "U8200") (pin "36") (pinfunction "ATXN3_36") (pintype "passive"))
    )
    (net (code "38") (name "/SATAPM0_TXN4") (class "Default")
      (node (ref "C8239") (pin "1") (pinfunction "1_1") (pintype "passive"))
      (node (ref "U8200") (pin "30") (pinfunction "ATXN4_30") (pintype "passive"))
    )
    (net (code "39") (name "/SATAPM0_TXN5") (class "Default")
      (node (ref "C8216") (pin "2") (pinfunction "2_2") (pintype "passive"))
      (node (ref "U8200") (pin "24") (pinfunction "ATXN5_24") (pintype "passive"))
    )
    (net (code "40") (name "/SATAPM0_TXN_0") (class "Default")
      (node (ref "C8215") (pin "2") (pinfunction "2_2") (pintype "passive"))
      (node (ref "J8202") (pin "3") (pinfunction "TXN_3") (pintype "passive"))
    )
    (net (code "41") (name "/SATAPM0_TXN_1") (class "Default")
      (node (ref "C8200") (pin "2") (pinfunction "2_2") (pintype "passive"))
      (node (ref "J8200") (pin "3") (pinfunction "TXN_3") (pintype "passive"))
    )
    (net (code "42") (name "/SATAPM0_TXN_2") (class "Default")
      (node (ref "C8206") (pin "2") (pinfunction "2_2") (pintype "passive"))
      (node (ref "J8201") (pin "3") (pinfunction "TXN_3") (pintype "passive"))
    )
    (net (code "43") (name "/SATAPM0_TXN_3") (class "Default")
      (node (ref "C8221") (pin "2") (pinfunction "2_2") (pintype "passive"))
      (node (ref "J8203") (pin "3") (pinfunction "TXN_3") (pintype "passive"))
    )
    (net (code "44") (name "/SATAPM0_TXN_4") (class "Default")
      (node (ref "C8239") (pin "2") (pinfunction "2_2") (pintype "passive"))
      (node (ref "J8204") (pin "3") (pinfunction "TXN_3") (pintype "passive"))
    )
    (net (code "45") (name "/SATAPM0_TXP0") (class "Default")
      (node (ref "C8214") (pin "1") (pinfunction "1_1") (pintype "passive"))
      (node (ref "U8200") (pin "48") (pinfunction "ATXP0_48") (pintype "passive"))
    )
    (net (code "46") (name "/SATAPM0_TXP1") (class "Default")
      (node (ref "C8201") (pin "1") (pinfunction "1_1") (pintype "passive"))
      (node (ref "U8200") (pin "60") (pinfunction "ATXP1_60") (pintype "passive"))
    )
    (net (code "47") (name "/SATAPM0_TXP2") (class "Default")
      (node (ref "C8205") (pin "1") (pinfunction "1_1") (pintype "passive"))
      (node (ref "U8200") (pin "54") (pinfunction "ATXP2_54") (pintype "passive"))
    )
    (net (code "48") (name "/SATAPM0_TXP3") (class "Default")
      (node (ref "C8220") (pin "1") (pinfunction "1_1") (pintype "passive"))
      (node (ref "U8200") (pin "37") (pinfunction "ATXP3_37") (pintype "passive"))
    )
    (net (code "49") (name "/SATAPM0_TXP4") (class "Default")
      (node (ref "C8238") (pin "1") (pinfunction "1_1") (pintype "passive"))
      (node (ref "U8200") (pin "31") (pinfunction "ATXP4_31") (pintype "passive"))
    )
    (net (code "50") (name "/SATAPM0_TXP5") (class "Default")
      (node (ref "C8218") (pin "2") (pinfunction "2_2") (pintype "passive"))
      (node (ref "U8200") (pin "25") (pinfunction "ATXP5_25") (pintype "passive"))
    )
    (net (code "51") (name "/SATAPM0_TXP_0") (class "Default")
      (node (ref "C8214") (pin "2") (pinfunction "2_2") (pintype "passive"))
      (node (ref "J8202") (pin "2") (pinfunction "TXP_2") (pintype "passive"))
    )
    (net (code "52") (name "/SATAPM0_TXP_1") (class "Default")
      (node (ref "C8201") (pin "2") (pinfunction "2_2") (pintype "passive"))
      (node (ref "J8200") (pin "2") (pinfunction "TXP_2") (pintype "passive"))
    )
    (net (code "53") (name "/SATAPM0_TXP_2") (class "Default")
      (node (ref "C8205") (pin "2") (pinfunction "2_2") (pintype "passive"))
      (node (ref "J8201") (pin "2") (pinfunction "TXP_2") (pintype "passive"))
    )
    (net (code "54") (name "/SATAPM0_TXP_3") (class "Default")
      (node (ref "C8220") (pin "2") (pinfunction "2_2") (pintype "passive"))
      (node (ref "J8203") (pin "2") (pinfunction "TXP_2") (pintype "passive"))
    )
    (net (code "55") (name "/SATAPM0_TXP_4") (class "Default")
      (node (ref "C8238") (pin "2") (pinfunction "2_2") (pintype "passive"))
      (node (ref "J8204") (pin "2") (pinfunction "TXP_2") (pintype "passive"))
    )
    (net (code "56") (name "/SATAPM0_XIN") (class "Default")
      (node (ref "C8213") (pin "1") (pinfunction "1_1") (pintype "passive"))
      (node (ref "R8207") (pin "2") (pinfunction "2_2") (pintype "passive"))
      (node (ref "U8200") (pin "39") (pinfunction "AXIN_39") (pintype "passive"))
      (node (ref "Y8200") (pin "3") (pinfunction "X2_3") (pintype "passive"))
    )
    (net (code "57") (name "/SATAPM0_XOUT") (class "Default")
      (node (ref "C8211") (pin "1") (pinfunction "1_1") (pintype "passive"))
      (node (ref "R8207") (pin "1") (pinfunction "1_1") (pintype "passive"))
      (node (ref "U8200") (pin "40") (pinfunction "AXOUT_40") (pintype "passive"))
      (node (ref "Y8200") (pin "1") (pinfunction "X1_1") (pintype "passive"))
    )
    (net (code "58") (name "GND") (class "Default")
      (node (ref "C8204") (pin "2") (pinfunction "2_2") (pintype "passive"))
      (node (ref "C8209") (pin "2") (pinfunction "2_2") (pintype "passive"))
      (node (ref "C8211") (pin "2") (pinfunction "2_2") (pintype "passive"))
      (node (ref "C8213") (pin "2") (pinfunction "2_2") (pintype "passive"))
      (node (ref "C8224") (pin "2") (pinfunction "2_2") (pintype "passive"))
      (node (ref "C8226") (pin "2") (pinfunction "2_2") (pintype "passive"))
      (node (ref "C8227") (pin "2") (pinfunction "2_2") (pintype "passive"))
      (node (ref "C8228") (pin "2") (pinfunction "2_2") (pintype "passive"))
      (node (ref "C8229") (pin "2") (pinfunction "2_2") (pintype "passive"))
      (node (ref "C8230") (pin "2") (pinfunction "2_2") (pintype "passive"))
      (node (ref "C8231") (pin "2") (pinfunction "2_2") (pintype "passive"))
      (node (ref "C8232") (pin "2") (pinfunction "2_2") (pintype "passive"))
      (node (ref "C8233") (pin "2") (pinfunction "2_2") (pintype "passive"))
      (node (ref "C8234") (pin "2") (pinfunction "2_2") (pintype "passive"))
      (node (ref "C8235") (pin "2") (pinfunction "2_2") (pintype "passive"))
      (node (ref "C8236") (pin "2") (pinfunction "2_2") (pintype "passive"))
      (node (ref "C8237") (pin "2") (pinfunction "2_2") (pintype "passive"))
      (node (ref "C8242") (pin "2") (pinfunction "2_2") (pintype "passive"))
      (node (ref "C8244") (pin "2") (pinfunction "2_2") (pintype "passive"))
      (node (ref "C8245") (pin "2") (pinfunction "2_2") (pintype "passive"))
      (node (ref "C8246") (pin "2") (pinfunction "2_2") (pintype "passive"))
      (node (ref "C8247") (pin "2") (pinfunction "2_2") (pintype "passive"))
      (node (ref "C8248") (pin "2") (pinfunction "2_2") (pintype "passive"))
      (node (ref "C8249") (pin "2") (pinfunction "2_2") (pintype "passive"))
      (node (ref "C8250") (pin "2") (pinfunction "2_2") (pintype "passive"))
      (node (ref "C8251") (pin "2") (pinfunction "2_2") (pintype "passive"))
      (node (ref "C8252") (pin "2") (pinfunction "2_2") (pintype "passive"))
      (node (ref "C8253") (pin "2") (pinfunction "2_2") (pintype "passive"))
      (node (ref "C8254") (pin "2") (pinfunction "2_2") (pintype "passive"))
      (node (ref "C8255") (pin "2") (pinfunction "2_2") (pintype "passive"))
      (node (ref "J8200") (pin "1") (pinfunction "GND1_1") (pintype "passive"))
      (node (ref "J8200") (pin "4") (pinfunction "GND2_4") (pintype "passive"))
      (node (ref "J8200") (pin "7") (pinfunction "GND3_7") (pintype "passive"))
      (node (ref "J8200") (pin "8") (pinfunction "GND4_8") (pintype "passive"))
      (node (ref "J8200") (pin "9") (pinfunction "GND5_9") (pintype "passive"))
      (node (ref "J8201") (pin "1") (pinfunction "GND1_1") (pintype "passive"))
      (node (ref "J8201") (pin "4") (pinfunction "GND2_4") (pintype "passive"))
      (node (ref "J8201") (pin "7") (pinfunction "GND3_7") (pintype "passive"))
      (node (ref "J8201") (pin "8") (pinfunction "GND4_8") (pintype "passive"))
      (node (ref "J8201") (pin "9") (pinfunction "GND5_9") (pintype "passive"))
      (node (ref "J8202") (pin "1") (pinfunction "GND1_1") (pintype "passive"))
      (node (ref "J8202") (pin "4") (pinfunction "GND2_4") (pintype "passive"))
      (node (ref "J8202") (pin "7") (pinfunction "GND3_7") (pintype "passive"))
      (node (ref "J8202") (pin "8") (pinfunction "GND4_8") (pintype "passive"))
      (node (ref "J8202") (pin "9") (pinfunction "GND5_9") (pintype "passive"))
      (node (ref "J8203") (pin "1") (pinfunction "GND1_1") (pintype "passive"))
      (node (ref "J8203") (pin "4") (pinfunction "GND2_4") (pintype "passive"))
      (node (ref "J8203") (pin "7") (pinfunction "GND3_7") (pintype "passive"))
      (node (ref "J8203") (pin "8") (pinfunction "GND4_8") (pintype "passive"))
      (node (ref "J8203") (pin "9") (pinfunction "GND5_9") (pintype "passive"))
      (node (ref "J8204") (pin "1") (pinfunction "GND1_1") (pintype "passive"))
      (node (ref "J8204") (pin "4") (pinfunction "GND2_4") (pintype "passive"))
      (node (ref "J8204") (pin "7") (pinfunction "GND3_7") (pintype "passive"))
      (node (ref "J8204") (pin "8") (pinfunction "GND4_8") (pintype "passive"))
      (node (ref "J8204") (pin "9") (pinfunction "GND5_9") (pintype "passive"))
      (node (ref "R8202") (pin "1") (pinfunction "1_1") (pintype "passive"))
      (node (ref "R8206") (pin "2") (pinfunction "2_2") (pintype "passive"))
      (node (ref "R8214") (pin "2") (pinfunction "2_2") (pintype "passive"))
      (node (ref "R8217") (pin "2") (pinfunction "2_2") (pintype "passive"))
      (node (ref "U8200") (pin "13") (pinfunction "DGND_2_13") (pintype "passive"))
      (node (ref "U8200") (pin "41") (pinfunction "AGNDC_41") (pintype "passive"))
      (node (ref "U8200") (pin "5") (pinfunction "DGND_1_5") (pintype "passive"))
      (node (ref "U8200") (pin "65") (pinfunction "EPAD_65") (pintype "passive"))
      (node (ref "U8201") (pin "4") (pinfunction "VSS_4") (pintype "passive"))
      (node (ref "U8201") (pin "9") (pinfunction "EPAD_9") (pintype "passive"))
      (node (ref "U8202") (pin "2") (pinfunction "GND_2") (pintype "passive"))
      (node (ref "U8203") (pin "2") (pinfunction "GND_2") (pintype "passive"))
      (node (ref "Y8200") (pin "2") (pinfunction "GND_2") (pintype "power_in"))
      (node (ref "Y8200") (pin "4") (pinfunction "GND_4") (pintype "power_in"))
    )
    (net (code "59") (name "Net-(U8202-EN)") (class "Default")
      (node (ref "C8237") (pin "1") (pinfunction "1_1") (pintype "passive"))
      (node (ref "R8212") (pin "2") (pinfunction "2_2") (pintype "passive"))
      (node (ref "U8202") (pin "1") (pinfunction "EN_1") (pintype "passive"))
    )
    (net (code "60") (name "Net-(U8202-FB{slash}OUT)") (class "Default")
      (node (ref "C8225") (pin "2") (pinfunction "2_2") (pintype "passive"))
      (node (ref "R8213") (pin "2") (pinfunction "2_2") (pintype "passive"))
      (node (ref "R8214") (pin "1") (pinfunction "1_1") (pintype "passive"))
      (node (ref "U8202") (pin "5") (pinfunction "FB/OUT_5") (pintype "passive"))
    )
    (net (code "61") (name "Net-(U8202-LX)") (class "Default")
      (node (ref "L8200") (pin "1") (pinfunction "1_1") (pintype "passive"))
      (node (ref "U8202") (pin "3") (pinfunction "LX_3") (pintype "passive"))
    )
    (net (code "62") (name "Net-(U8203-EN)") (class "Default")
      (node (ref "C8255") (pin "1") (pinfunction "1_1") (pintype "passive"))
      (node (ref "R8215") (pin "2") (pinfunction "2_2") (pintype "passive"))
      (node (ref "U8203") (pin "1") (pinfunction "EN_1") (pintype "passive"))
    )
    (net (code "63") (name "Net-(U8203-FB{slash}OUT)") (class "Default")
      (node (ref "C8243") (pin "2") (pinfunction "2_2") (pintype "passive"))
      (node (ref "R8216") (pin "2") (pinfunction "2_2") (pintype "passive"))
      (node (ref "R8217") (pin "1") (pinfunction "1_1") (pintype "passive"))
      (node (ref "U8203") (pin "5") (pinfunction "FB/OUT_5") (pintype "passive"))
    )
    (net (code "64") (name "Net-(U8203-LX)") (class "Default")
      (node (ref "L8201") (pin "1") (pinfunction "1_1") (pintype "passive"))
      (node (ref "U8203") (pin "3") (pinfunction "LX_3") (pintype "passive"))
    )
    (net (code "65") (name "SATA30_0_RXN") (class "Default")
      (node (ref "C8216") (pin "1") (pinfunction "1_1") (pintype "passive"))
    )
    (net (code "66") (name "SATA30_0_RXP") (class "Default")
      (node (ref "C8218") (pin "1") (pinfunction "1_1") (pintype "passive"))
    )
    (net (code "67") (name "SATA30_0_TXN") (class "Default")
      (node (ref "C8210") (pin "1") (pinfunction "1_1") (pintype "passive"))
    )
    (net (code "68") (name "SATA30_0_TXP") (class "Default")
      (node (ref "C8212") (pin "1") (pinfunction "1_1") (pintype "passive"))
    )
    (net (code "69") (name "SATAPM0_RSTn_L_GPIO4_A0") (class "Default")
      (node (ref "R8201") (pin "1") (pinfunction "1_1") (pintype "passive"))
    )
    (net (code "70") (name "VCC3V3_SATAPM0") (class "Default")
      (node (ref "C8209") (pin "1") (pinfunction "1_1") (pintype "passive"))
      (node (ref "C8225") (pin "1") (pinfunction "1_1") (pintype "passive"))
      (node (ref "C8226") (pin "1") (pinfunction "1_1") (pintype "passive"))
      (node (ref "C8227") (pin "1") (pinfunction "1_1") (pintype "passive"))
      (node (ref "C8228") (pin "1") (pinfunction "1_1") (pintype "passive"))
      (node (ref "C8229") (pin "1") (pinfunction "1_1") (pintype "passive"))
      (node (ref "C8230") (pin "1") (pinfunction "1_1") (pintype "passive"))
      (node (ref "C8231") (pin "1") (pinfunction "1_1") (pintype "passive"))
      (node (ref "C8232") (pin "1") (pinfunction "1_1") (pintype "passive"))
      (node (ref "C8233") (pin "1") (pinfunction "1_1") (pintype "passive"))
      (node (ref "C8234") (pin "1") (pinfunction "1_1") (pintype "passive"))
      (node (ref "C8235") (pin "1") (pinfunction "1_1") (pintype "passive"))
      (node (ref "C8236") (pin "1") (pinfunction "1_1") (pintype "passive"))
      (node (ref "L8200") (pin "2") (pinfunction "2_2") (pintype "passive"))
      (node (ref "R8200") (pin "1") (pinfunction "1_1") (pintype "passive"))
      (node (ref "R8203") (pin "1") (pinfunction "1_1") (pintype "passive"))
      (node (ref "R8204") (pin "1") (pinfunction "1_1") (pintype "passive"))
      (node (ref "R8205") (pin "1") (pinfunction "1_1") (pintype "passive"))
      (node (ref "R8208") (pin "1") (pinfunction "1_1") (pintype "passive"))
      (node (ref "R8209") (pin "1") (pinfunction "1_1") (pintype "passive"))
      (node (ref "R8210") (pin "1") (pinfunction "1_1") (pintype "passive"))
      (node (ref "R8211") (pin "2") (pinfunction "2_2") (pintype "passive"))
      (node (ref "R8213") (pin "1") (pinfunction "1_1") (pintype "passive"))
      (node (ref "R8215") (pin "1") (pinfunction "1_1") (pintype "passive"))
      (node (ref "U8200") (pin "12") (pinfunction "DV33_2_12") (pintype "passive"))
      (node (ref "U8200") (pin "26") (pinfunction "AV33_5_26") (pintype "passive"))
      (node (ref "U8200") (pin "32") (pinfunction "AV33_4_32") (pintype "passive"))
      (node (ref "U8200") (pin "38") (pinfunction "AV33_3_38") (pintype "passive"))
      (node (ref "U8200") (pin "43") (pinfunction "AV33_C_43") (pintype "passive"))
      (node (ref "U8200") (pin "49") (pinfunction "AV33_0_49") (pintype "passive"))
      (node (ref "U8200") (pin "55") (pinfunction "AV33_2_55") (pintype "passive"))
      (node (ref "U8200") (pin "6") (pinfunction "DV33_1_6") (pintype "passive"))
      (node (ref "U8200") (pin "61") (pinfunction "AV33_1_61") (pintype "passive"))
      (node (ref "U8201") (pin "8") (pinfunction "VCC_8") (pintype "passive"))
    )
    (net (code "71") (name "VCC4V0_SYS") (class "Default")
      (node (ref "C8224") (pin "1") (pinfunction "1_1") (pintype "passive"))
      (node (ref "C8242") (pin "1") (pinfunction "1_1") (pintype "passive"))
      (node (ref "R8212") (pin "1") (pinfunction "1_1") (pintype "passive"))
      (node (ref "U8202") (pin "4") (pinfunction "VIN_4") (pintype "passive"))
      (node (ref "U8203") (pin "4") (pinfunction "VIN_4") (pintype "passive"))
    )
    (net (code "72") (name "VCC_3V3") (class "Default")
      (node (ref "R8211") (pin "1") (pinfunction "1_1") (pintype "passive"))
    )
    (net (code "73") (name "VDD1V2_SATAPM0") (class "Default")
      (node (ref "C8243") (pin "1") (pinfunction "1_1") (pintype "passive"))
      (node (ref "C8244") (pin "1") (pinfunction "1_1") (pintype "passive"))
      (node (ref "C8245") (pin "1") (pinfunction "1_1") (pintype "passive"))
      (node (ref "C8246") (pin "1") (pinfunction "1_1") (pintype "passive"))
      (node (ref "C8247") (pin "1") (pinfunction "1_1") (pintype "passive"))
      (node (ref "C8248") (pin "1") (pinfunction "1_1") (pintype "passive"))
      (node (ref "C8249") (pin "1") (pinfunction "1_1") (pintype "passive"))
      (node (ref "C8250") (pin "1") (pinfunction "1_1") (pintype "passive"))
      (node (ref "C8251") (pin "1") (pinfunction "1_1") (pintype "passive"))
      (node (ref "C8252") (pin "1") (pinfunction "1_1") (pintype "passive"))
      (node (ref "C8253") (pin "1") (pinfunction "1_1") (pintype "passive"))
      (node (ref "C8254") (pin "1") (pinfunction "1_1") (pintype "passive"))
      (node (ref "L8201") (pin "2") (pinfunction "2_2") (pintype "passive"))
      (node (ref "R8216") (pin "1") (pinfunction "1_1") (pintype "passive"))
      (node (ref "U8200") (pin "14") (pinfunction "DV12_2_14") (pintype "passive"))
      (node (ref "U8200") (pin "23") (pinfunction "AV12_5_23") (pintype "passive"))
      (node (ref "U8200") (pin "29") (pinfunction "AV12_4_29") (pintype "passive"))
      (node (ref "U8200") (pin "35") (pinfunction "AV12_3_35") (pintype "passive"))
      (node (ref "U8200") (pin "4") (pinfunction "DV12_1_4") (pintype "passive"))
      (node (ref "U8200") (pin "46") (pinfunction "AV12_0_46") (pintype "passive"))
      (node (ref "U8200") (pin "52") (pinfunction "AV12_2_52") (pintype "passive"))
      (node (ref "U8200") (pin "58") (pinfunction "AV12_1_58") (pintype "passive"))
    )
    (net (code "74") (name "unconnected-(U8200-ZGPIO05-Pad9)") (class "Default")
      (node (ref "U8200") (pin "9") (pinfunction "ZGPIO05_9") (pintype "passive+no_connect"))
    )
    (net (code "75") (name "unconnected-(U8200-ZGPIO06-Pad8)") (class "Default")
      (node (ref "U8200") (pin "8") (pinfunction "ZGPIO06_8") (pintype "passive+no_connect"))
    )
    (net (code "76") (name "unconnected-(U8200-ZGPIO07-Pad7)") (class "Default")
      (node (ref "U8200") (pin "7") (pinfunction "ZGPIO07_7") (pintype "passive+no_connect"))
    )
    (net (code "77") (name "unconnected-(U8200-ZGPIO08-Pad3)") (class "Default")
      (node (ref "U8200") (pin "3") (pinfunction "ZGPIO08_3") (pintype "passive+no_connect"))
    )
    (net (code "78") (name "unconnected-(U8200-ZGPIO09-Pad2)") (class "Default")
      (node (ref "U8200") (pin "2") (pinfunction "ZGPIO09_2") (pintype "passive+no_connect"))
    )
    (net (code "79") (name "unconnected-(U8200-ZGPIO10-Pad1)") (class "Default")
      (node (ref "U8200") (pin "1") (pinfunction "ZGPIO10_1") (pintype "passive+no_connect"))
    )
    (net (code "80") (name "unconnected-(U8200-ZGPIO11-Pad64)") (class "Default")
      (node (ref "U8200") (pin "64") (pinfunction "ZGPIO11_64") (pintype "passive+no_connect"))
    )
  )
)
